# kartSPKR_rev_0.net
KiCad netlist of a schematic drawn in EAGLE
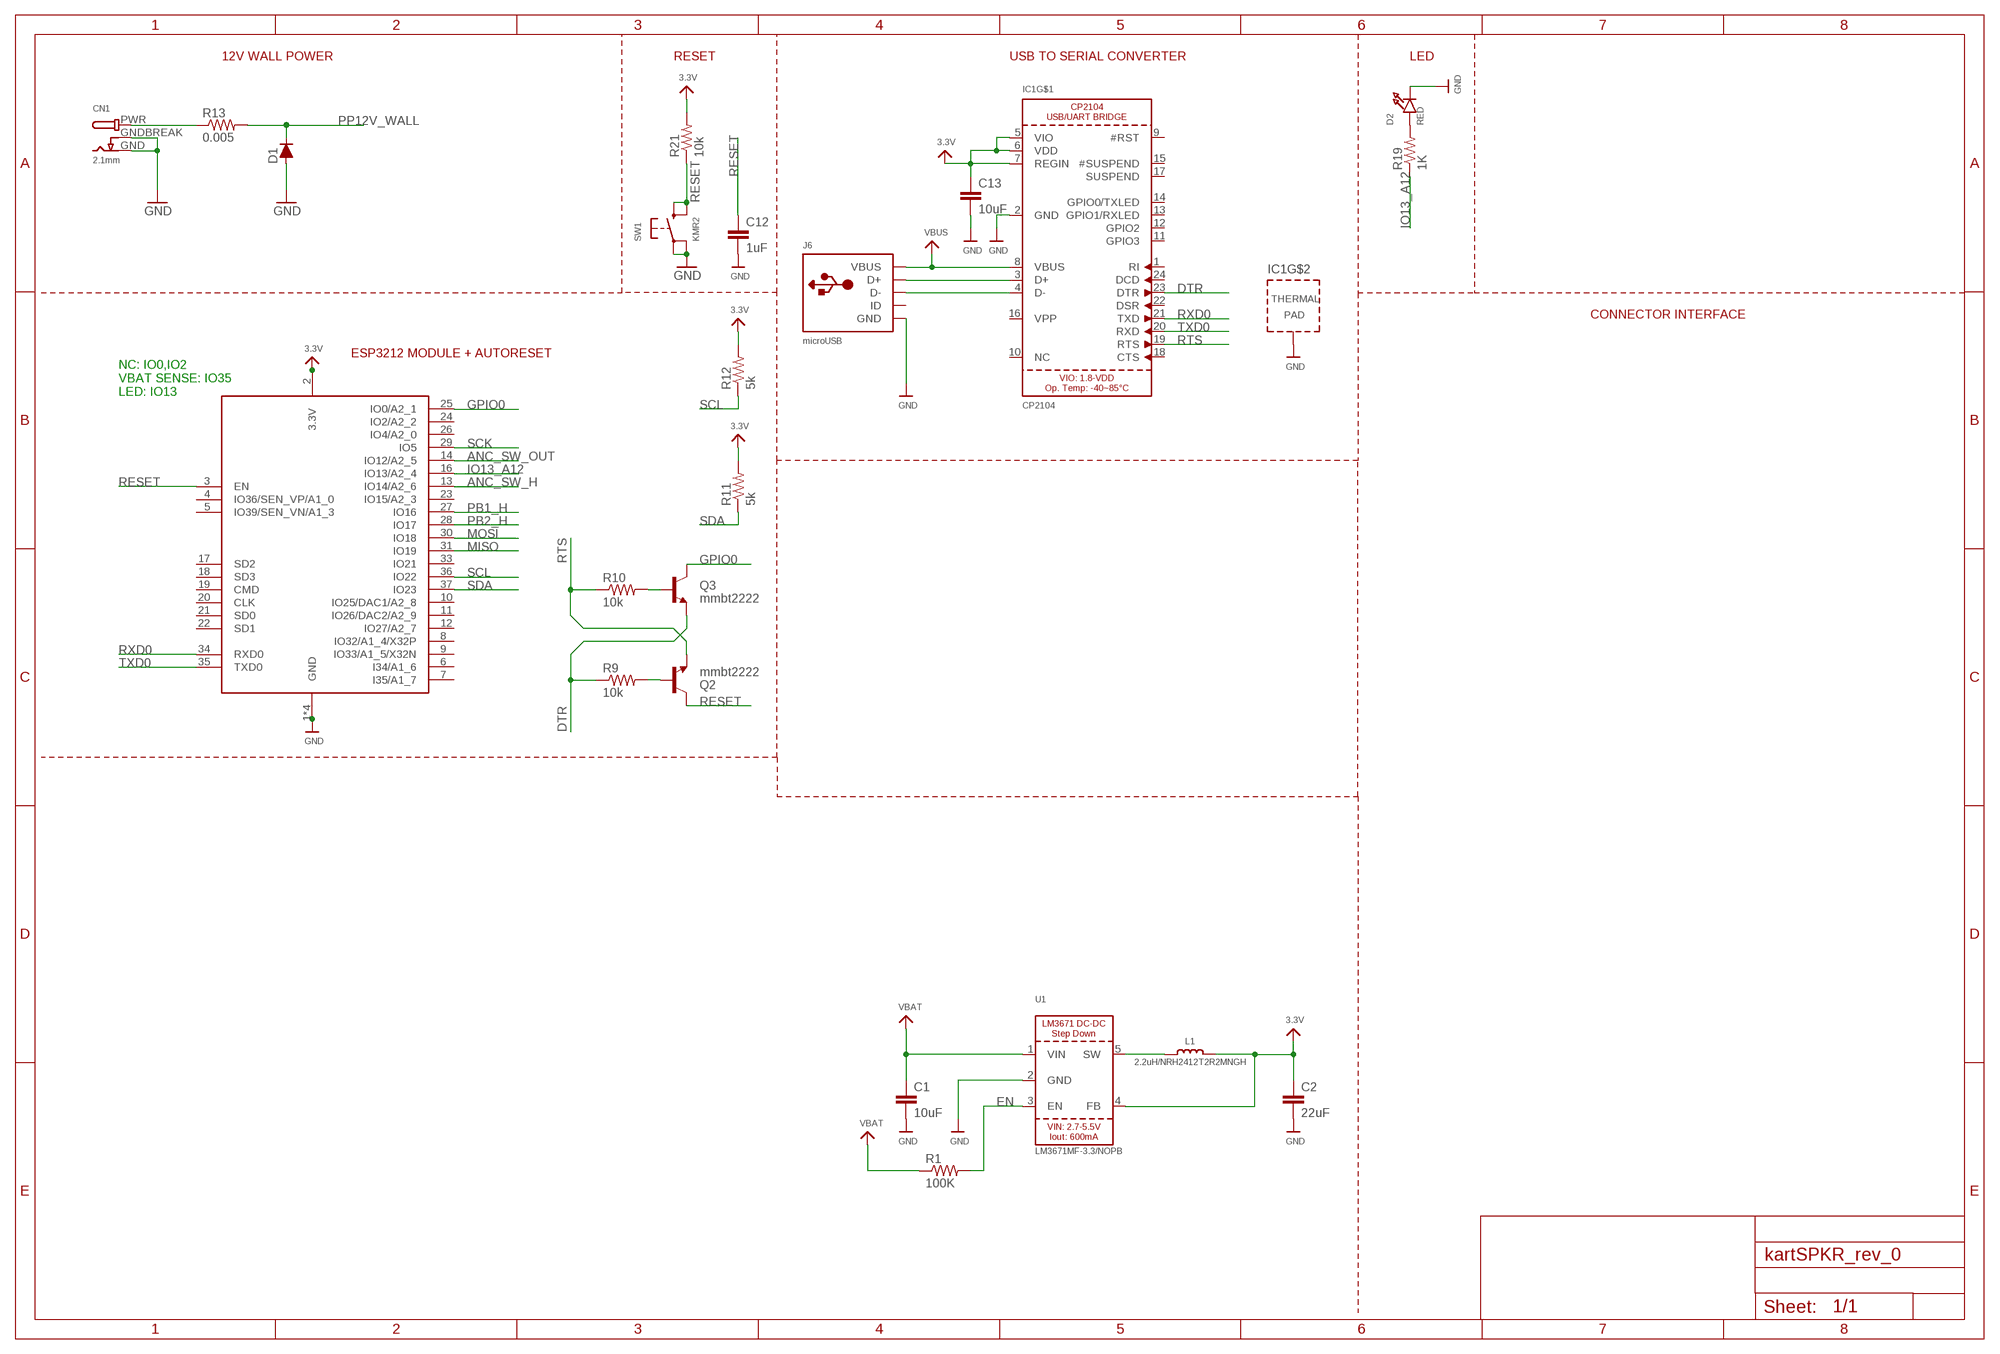
[diagram p0: schematic, sheet 1]

(export (version "E")
  (design (tool "Eeschema 10.0.6"))
  (components
    (comp (ref "C1")
      (value "10uF")
      (footprint "eagle-import:C0603")
      (libsource (lib "eagle-import") (part "C-EUC0603"))
    )
    (comp (ref "C2")
      (value "22uF")
      (footprint "eagle-import:C0603")
      (libsource (lib "eagle-import") (part "C-EUC0603"))
    )
    (comp (ref "C12")
      (value "1uF")
      (footprint "eagle-import:C0603")
      (libsource (lib "eagle-import") (part "C-EUC0603"))
    )
    (comp (ref "C13")
      (value "10uF")
      (footprint "eagle-import:C0603")
      (libsource (lib "eagle-import") (part "C-EUC0603"))
    )
    (comp (ref "CN1")
      (value "2.1mm")
      (footprint "eagle-import:DCJACK_2MM_SMT")
      (libsource (lib "eagle-import") (part "DCBARRELSMT_CORRECT"))
    )
    (comp (ref "D1")
      (value "D-FILL-SMB")
      (footprint "eagle-import:SMB")
      (libsource (lib "eagle-import") (part "D-FILL-SMB"))
    )
    (comp (ref "D2")
      (value "RED")
      (footprint "eagle-import:CHIPLED_0805_NOOUTLINE")
      (libsource (lib "eagle-import") (part "LED0805_NOOUTLINE"))
    )
    (comp (ref "IC1")
      (value "CP2104")
      (footprint "eagle-import:QFN24_4MM_SMSC")
      (libsource (lib "eagle-import") (part "CP2104"))
    )
    (comp (ref "J6")
      (value "microUSB")
      (footprint "eagle-import:4UCONN_20329")
      (libsource (lib "eagle-import") (part "USBMICRO_20329"))
    )
    (comp (ref "L1")
      (value "2.2uH/NRH2412T2R2MNGH")
      (footprint "eagle-import:INDUCTOR_TAIYOYUDEN_NRH2412T")
      (libsource (lib "eagle-import") (part "INDUCTORNRH2412T"))
    )
    (comp (ref "Q2")
      (value "mmbt2222")
      (footprint "eagle-import:SOT23-3")
      (libsource (lib "eagle-import") (part "TRANSISTOR_NPNSOT23-3"))
    )
    (comp (ref "Q3")
      (value "mmbt2222")
      (footprint "eagle-import:SOT23-3")
      (libsource (lib "eagle-import") (part "TRANSISTOR_NPNSOT23-3"))
    )
    (comp (ref "R1")
      (value "100K")
      (footprint "eagle-import:R0603")
      (libsource (lib "eagle-import") (part "R-US_R0603"))
    )
    (comp (ref "R9")
      (value "10k")
      (footprint "eagle-import:R0603")
      (libsource (lib "eagle-import") (part "R-US_R0603"))
    )
    (comp (ref "R10")
      (value "10k")
      (footprint "eagle-import:R0603")
      (libsource (lib "eagle-import") (part "R-US_R0603"))
    )
    (comp (ref "R11")
      (value "5k")
      (footprint "eagle-import:R0603")
      (libsource (lib "eagle-import") (part "R-US_R0603"))
    )
    (comp (ref "R12")
      (value "5k")
      (footprint "eagle-import:R0603")
      (libsource (lib "eagle-import") (part "R-US_R0603"))
    )
    (comp (ref "R13")
      (value "0.005")
      (footprint "eagle-import:R1206")
      (libsource (lib "eagle-import") (part "R-US_R1206"))
    )
    (comp (ref "R19")
      (value "1K")
      (footprint "eagle-import:R0603")
      (libsource (lib "eagle-import") (part "R-US_R0603"))
    )
    (comp (ref "R21")
      (value "10k")
      (footprint "eagle-import:R0603")
      (libsource (lib "eagle-import") (part "R-US_R0603"))
    )
    (comp (ref "SW1")
      (value "KMR2")
      (footprint "eagle-import:BTN_KMR2_4.6X2.8")
      (libsource (lib "eagle-import") (part "SWITCH_TACT_SMT4.6X2.8"))
    )
    (comp (ref "U1")
      (value "LM3671MF-3.3/NOPB")
      (footprint "eagle-import:SOT23-5")
      (libsource (lib "eagle-import") (part "VREG_LM3671"))
    )
    (comp (ref "X1")
      (value "ESP32_WROOM32_SKINNY")
      (footprint "eagle-import:WROOM32_SKINNY")
      (libsource (lib "eagle-import") (part "ESP32_WROOM32_SKINNY"))
    )
  )
  (nets
    (net (code "1") (name "/ANC_SW_H") (class "Default")
      (node (ref "X1") (pin "13") (pinfunction "IO14/A2_6_13") (pintype "bidirectional"))
    )
    (net (code "2") (name "/ANC_SW_OUT") (class "Default")
      (node (ref "X1") (pin "14") (pinfunction "IO12/A2_5_14") (pintype "bidirectional"))
    )
    (net (code "3") (name "/DTR") (class "Default")
      (node (ref "IC1") (pin "23") (pinfunction "DTR_23") (pintype "output"))
      (node (ref "Q3") (pin "2") (pinfunction "E_2") (pintype "passive"))
      (node (ref "R9") (pin "1") (pinfunction "1_1") (pintype "passive"))
    )
    (net (code "4") (name "/EN") (class "Default")
      (node (ref "R1") (pin "2") (pinfunction "2_2") (pintype "passive"))
      (node (ref "U1") (pin "3") (pinfunction "EN_3") (pintype "input"))
    )
    (net (code "5") (name "/GPIO0") (class "Default")
      (node (ref "Q3") (pin "3") (pinfunction "C_3") (pintype "passive"))
      (node (ref "X1") (pin "25") (pinfunction "IO0/A2_1_25") (pintype "bidirectional"))
    )
    (net (code "6") (name "/IO13_A12") (class "Default")
      (node (ref "R19") (pin "1") (pinfunction "1_1") (pintype "passive"))
      (node (ref "X1") (pin "16") (pinfunction "IO13/A2_4_16") (pintype "bidirectional"))
    )
    (net (code "7") (name "/MISO") (class "Default")
      (node (ref "X1") (pin "31") (pinfunction "IO19_31") (pintype "bidirectional"))
    )
    (net (code "8") (name "/MOSI") (class "Default")
      (node (ref "X1") (pin "30") (pinfunction "IO18_30") (pintype "bidirectional"))
    )
    (net (code "9") (name "/PB1_H") (class "Default")
      (node (ref "X1") (pin "27") (pinfunction "IO16_27") (pintype "bidirectional"))
    )
    (net (code "10") (name "/PB2_H") (class "Default")
      (node (ref "X1") (pin "28") (pinfunction "IO17_28") (pintype "bidirectional"))
    )
    (net (code "11") (name "/PP12V_WALL") (class "Default")
      (node (ref "D1") (pin "1") (pinfunction "C_1") (pintype "passive"))
      (node (ref "R13") (pin "2") (pinfunction "2_2") (pintype "passive"))
    )
    (net (code "12") (name "/RESET") (class "Default")
      (node (ref "C12") (pin "1") (pinfunction "1_1") (pintype "passive"))
      (node (ref "Q2") (pin "3") (pinfunction "C_3") (pintype "passive"))
      (node (ref "R21") (pin "1") (pinfunction "1_1") (pintype "passive"))
      (node (ref "SW1") (pin "B") (pinfunction "S_B") (pintype "passive"))
      (node (ref "SW1") (pin "B'") (pinfunction "S1_B'") (pintype "passive"))
      (node (ref "X1") (pin "3") (pinfunction "EN_3") (pintype "input"))
    )
    (net (code "13") (name "/RTS") (class "Default")
      (node (ref "IC1") (pin "19") (pinfunction "RTS_19") (pintype "output"))
      (node (ref "Q2") (pin "2") (pinfunction "E_2") (pintype "passive"))
      (node (ref "R10") (pin "1") (pinfunction "1_1") (pintype "passive"))
    )
    (net (code "14") (name "/RXD0") (class "Default")
      (node (ref "IC1") (pin "21") (pinfunction "TXD_21") (pintype "output"))
      (node (ref "X1") (pin "34") (pinfunction "RXD0_34") (pintype "input"))
    )
    (net (code "15") (name "/SCK") (class "Default")
      (node (ref "X1") (pin "29") (pinfunction "IO5_29") (pintype "bidirectional"))
    )
    (net (code "16") (name "/SCL") (class "Default")
      (node (ref "R12") (pin "1") (pinfunction "1_1") (pintype "passive"))
      (node (ref "X1") (pin "36") (pinfunction "IO22_36") (pintype "bidirectional"))
    )
    (net (code "17") (name "/SDA") (class "Default")
      (node (ref "R11") (pin "1") (pinfunction "1_1") (pintype "passive"))
      (node (ref "X1") (pin "37") (pinfunction "IO23_37") (pintype "bidirectional"))
    )
    (net (code "18") (name "/TXD0") (class "Default")
      (node (ref "IC1") (pin "20") (pinfunction "RXD_20") (pintype "input"))
      (node (ref "X1") (pin "35") (pinfunction "TXD0_35") (pintype "output"))
    )
    (net (code "19") (name "3.3V") (class "Default")
      (node (ref "C13") (pin "1") (pinfunction "1_1") (pintype "passive"))
      (node (ref "C2") (pin "1") (pinfunction "1_1") (pintype "passive"))
      (node (ref "IC1") (pin "5") (pinfunction "VIO_5") (pintype "power_in"))
      (node (ref "IC1") (pin "6") (pinfunction "VDD_6") (pintype "power_in"))
      (node (ref "IC1") (pin "7") (pinfunction "REGIN_7") (pintype "power_in"))
      (node (ref "L1") (pin "2") (pinfunction "2_2") (pintype "passive"))
      (node (ref "R11") (pin "2") (pinfunction "2_2") (pintype "passive"))
      (node (ref "R12") (pin "2") (pinfunction "2_2") (pintype "passive"))
      (node (ref "R21") (pin "2") (pinfunction "2_2") (pintype "passive"))
      (node (ref "U1") (pin "4") (pinfunction "FB_4") (pintype "power_in"))
      (node (ref "X1") (pin "2") (pinfunction "3.3V_2") (pintype "passive"))
    )
    (net (code "20") (name "GND") (class "Default")
      (node (ref "C1") (pin "2") (pinfunction "2_2") (pintype "passive"))
      (node (ref "C12") (pin "2") (pinfunction "2_2") (pintype "passive"))
      (node (ref "C13") (pin "2") (pinfunction "2_2") (pintype "passive"))
      (node (ref "C2") (pin "2") (pinfunction "2_2") (pintype "passive"))
      (node (ref "CN1") (pin "GND") (pinfunction "GND_GND") (pintype "power_in"))
      (node (ref "CN1") (pin "GNDBREAK") (pinfunction "GNDBREAK_GNDBREAK") (pintype "power_in"))
      (node (ref "D1") (pin "2") (pinfunction "A_2") (pintype "passive"))
      (node (ref "D2") (pin "C") (pinfunction "C_C") (pintype "passive"))
      (node (ref "IC1") (pin "2") (pinfunction "GND_2") (pintype "power_in"))
      (node (ref "IC1") (pin "THERM") (pinfunction "TP_THERM") (pintype "power_in"))
      (node (ref "J6") (pin "BASE@1") (pinfunction "GND_BASE@1") (pintype "power_in"))
      (node (ref "J6") (pin "BASE@2") (pinfunction "GND_BASE@2") (pintype "power_in"))
      (node (ref "J6") (pin "GND") (pinfunction "GND_GND") (pintype "power_in"))
      (node (ref "J6") (pin "SPRT@1") (pinfunction "GND_SPRT@1") (pintype "power_in"))
      (node (ref "J6") (pin "SPRT@2") (pinfunction "GND_SPRT@2") (pintype "power_in"))
      (node (ref "J6") (pin "SPRT@3") (pinfunction "GND_SPRT@3") (pintype "power_in"))
      (node (ref "J6") (pin "SPRT@4") (pinfunction "GND_SPRT@4") (pintype "power_in"))
      (node (ref "SW1") (pin "A") (pinfunction "P_A") (pintype "passive"))
      (node (ref "SW1") (pin "A'") (pinfunction "P1_A'") (pintype "passive"))
      (node (ref "U1") (pin "2") (pinfunction "GND_2") (pintype "power_in"))
      (node (ref "X1") (pin "1") (pinfunction "GND_1") (pintype "passive"))
      (node (ref "X1") (pin "15") (pinfunction "GND_15") (pintype "passive"))
      (node (ref "X1") (pin "38") (pinfunction "GND_38") (pintype "passive"))
      (node (ref "X1") (pin "P$1") (pinfunction "GND_P$1") (pintype "passive"))
    )
    (net (code "21") (name "Net-(CN1-PadPWR)") (class "Default")
      (node (ref "CN1") (pin "PWR") (pinfunction "PWR_PWR") (pintype "power_in"))
      (node (ref "R13") (pin "1") (pinfunction "1_1") (pintype "passive"))
    )
    (net (code "22") (name "Net-(D2-PadA)") (class "Default")
      (node (ref "D2") (pin "A") (pinfunction "A_A") (pintype "passive"))
      (node (ref "R19") (pin "2") (pinfunction "2_2") (pintype "passive"))
    )
    (net (code "23") (name "Net-(IC1A-D+)") (class "Default")
      (node (ref "IC1") (pin "3") (pinfunction "D+_3") (pintype "bidirectional"))
      (node (ref "J6") (pin "D+") (pinfunction "D+_D+") (pintype "bidirectional"))
    )
    (net (code "24") (name "Net-(IC1A-D-)") (class "Default")
      (node (ref "IC1") (pin "4") (pinfunction "D-_4") (pintype "bidirectional"))
      (node (ref "J6") (pin "D-") (pinfunction "D-_D-") (pintype "bidirectional"))
    )
    (net (code "25") (name "Net-(Q2-B)") (class "Default")
      (node (ref "Q2") (pin "1") (pinfunction "B_1") (pintype "passive"))
      (node (ref "R9") (pin "2") (pinfunction "2_2") (pintype "passive"))
    )
    (net (code "26") (name "Net-(Q3-B)") (class "Default")
      (node (ref "Q3") (pin "1") (pinfunction "B_1") (pintype "passive"))
      (node (ref "R10") (pin "2") (pinfunction "2_2") (pintype "passive"))
    )
    (net (code "27") (name "Net-(U1-SW)") (class "Default")
      (node (ref "L1") (pin "1") (pinfunction "1_1") (pintype "passive"))
      (node (ref "U1") (pin "5") (pinfunction "SW_5") (pintype "output"))
    )
    (net (code "28") (name "VBAT") (class "Default")
      (node (ref "C1") (pin "1") (pinfunction "1_1") (pintype "passive"))
      (node (ref "R1") (pin "1") (pinfunction "1_1") (pintype "passive"))
      (node (ref "U1") (pin "1") (pinfunction "VIN_1") (pintype "power_in"))
    )
    (net (code "29") (name "VBUS") (class "Default")
      (node (ref "IC1") (pin "8") (pinfunction "VBUS_8") (pintype "power_in"))
      (node (ref "J6") (pin "VBUS") (pinfunction "VBUS_VBUS") (pintype "power_in"))
    )
    (net (code "30") (name "unconnected-(IC1A-#RST-Pad9)") (class "Default")
      (node (ref "IC1") (pin "9") (pinfunction "#RST_9") (pintype "bidirectional"))
    )
    (net (code "31") (name "unconnected-(IC1A-#SUSPEND-Pad15)") (class "Default")
      (node (ref "IC1") (pin "15") (pinfunction "#SUSPEND_15") (pintype "output"))
    )
    (net (code "32") (name "unconnected-(IC1A-CTS-Pad18)") (class "Default")
      (node (ref "IC1") (pin "18") (pinfunction "CTS_18") (pintype "input"))
    )
    (net (code "33") (name "unconnected-(IC1A-DCD-Pad24)") (class "Default")
      (node (ref "IC1") (pin "24") (pinfunction "DCD_24") (pintype "input"))
    )
    (net (code "34") (name "unconnected-(IC1A-DSR-Pad22)") (class "Default")
      (node (ref "IC1") (pin "22") (pinfunction "DSR_22") (pintype "input"))
    )
    (net (code "35") (name "unconnected-(IC1A-GPIO0{slash}TXLED-Pad14)") (class "Default")
      (node (ref "IC1") (pin "14") (pinfunction "GPIO0/TXLED_14") (pintype "bidirectional"))
    )
    (net (code "36") (name "unconnected-(IC1A-GPIO1{slash}RXLED-Pad13)") (class "Default")
      (node (ref "IC1") (pin "13") (pinfunction "GPIO1/RXLED_13") (pintype "bidirectional"))
    )
    (net (code "37") (name "unconnected-(IC1A-GPIO2-Pad12)") (class "Default")
      (node (ref "IC1") (pin "12") (pinfunction "GPIO2_12") (pintype "bidirectional"))
    )
    (net (code "38") (name "unconnected-(IC1A-GPIO3-Pad11)") (class "Default")
      (node (ref "IC1") (pin "11") (pinfunction "GPIO3_11") (pintype "bidirectional"))
    )
    (net (code "39") (name "unconnected-(IC1A-NC-Pad10)") (class "Default")
      (node (ref "IC1") (pin "10") (pinfunction "NC_10") (pintype "no_connect"))
    )
    (net (code "40") (name "unconnected-(IC1A-RI-Pad1)") (class "Default")
      (node (ref "IC1") (pin "1") (pinfunction "RI_1") (pintype "input"))
    )
    (net (code "41") (name "unconnected-(IC1A-SUSPEND-Pad17)") (class "Default")
      (node (ref "IC1") (pin "17") (pinfunction "SUSPEND_17") (pintype "output"))
    )
    (net (code "42") (name "unconnected-(IC1A-VPP-Pad16)") (class "Default")
      (node (ref "IC1") (pin "16") (pinfunction "VPP_16") (pintype "bidirectional"))
    )
    (net (code "43") (name "unconnected-(J6-PadID)") (class "Default")
      (node (ref "J6") (pin "ID") (pinfunction "ID_ID") (pintype "bidirectional"))
    )
    (net (code "44") (name "unconnected-(X1-CLK-Pad20)") (class "Default")
      (node (ref "X1") (pin "20") (pinfunction "CLK_20") (pintype "bidirectional"))
    )
    (net (code "45") (name "unconnected-(X1-CMD-Pad19)") (class "Default")
      (node (ref "X1") (pin "19") (pinfunction "CMD_19") (pintype "bidirectional"))
    )
    (net (code "46") (name "unconnected-(X1-I34{slash}A1_6-Pad6)") (class "Default")
      (node (ref "X1") (pin "6") (pinfunction "I34/A1_6_6") (pintype "bidirectional"))
    )
    (net (code "47") (name "unconnected-(X1-I35{slash}A1_7-Pad7)") (class "Default")
      (node (ref "X1") (pin "7") (pinfunction "I35/A1_7_7") (pintype "bidirectional"))
    )
    (net (code "48") (name "unconnected-(X1-IO2{slash}A2_2-Pad24)") (class "Default")
      (node (ref "X1") (pin "24") (pinfunction "IO2/A2_2_24") (pintype "bidirectional"))
    )
    (net (code "49") (name "unconnected-(X1-IO4{slash}A2_0-Pad26)") (class "Default")
      (node (ref "X1") (pin "26") (pinfunction "IO4/A2_0_26") (pintype "bidirectional"))
    )
    (net (code "50") (name "unconnected-(X1-IO15{slash}A2_3-Pad23)") (class "Default")
      (node (ref "X1") (pin "23") (pinfunction "IO15/A2_3_23") (pintype "bidirectional"))
    )
    (net (code "51") (name "unconnected-(X1-IO21-Pad33)") (class "Default")
      (node (ref "X1") (pin "33") (pinfunction "IO21_33") (pintype "bidirectional"))
    )
    (net (code "52") (name "unconnected-(X1-IO25{slash}DAC1{slash}A2_8-Pad10)") (class "Default")
      (node (ref "X1") (pin "10") (pinfunction "IO25/DAC1/A2_8_10") (pintype "bidirectional"))
    )
    (net (code "53") (name "unconnected-(X1-IO26{slash}DAC2{slash}A2_9-Pad11)") (class "Default")
      (node (ref "X1") (pin "11") (pinfunction "IO26/DAC2/A2_9_11") (pintype "bidirectional"))
    )
    (net (code "54") (name "unconnected-(X1-IO27{slash}A2_7-Pad12)") (class "Default")
      (node (ref "X1") (pin "12") (pinfunction "IO27/A2_7_12") (pintype "bidirectional"))
    )
    (net (code "55") (name "unconnected-(X1-IO32{slash}A1_4{slash}X32P-Pad8)") (class "Default")
      (node (ref "X1") (pin "8") (pinfunction "IO32/A1_4/X32P_8") (pintype "bidirectional"))
    )
    (net (code "56") (name "unconnected-(X1-IO33{slash}A1_5{slash}X32N-Pad9)") (class "Default")
      (node (ref "X1") (pin "9") (pinfunction "IO33/A1_5/X32N_9") (pintype "bidirectional"))
    )
    (net (code "57") (name "unconnected-(X1-IO36{slash}SEN_VP{slash}A1_0-Pad4)") (class "Default")
      (node (ref "X1") (pin "4") (pinfunction "IO36/SEN_VP/A1_0_4") (pintype "passive"))
    )
    (net (code "58") (name "unconnected-(X1-IO39{slash}SEN_VN{slash}A1_3-Pad5)") (class "Default")
      (node (ref "X1") (pin "5") (pinfunction "IO39/SEN_VN/A1_3_5") (pintype "passive"))
    )
    (net (code "59") (name "unconnected-(X1-SD0-Pad21)") (class "Default")
      (node (ref "X1") (pin "21") (pinfunction "SD0_21") (pintype "bidirectional"))
    )
    (net (code "60") (name "unconnected-(X1-SD1-Pad22)") (class "Default")
      (node (ref "X1") (pin "22") (pinfunction "SD1_22") (pintype "bidirectional"))
    )
    (net (code "61") (name "unconnected-(X1-SD2-Pad17)") (class "Default")
      (node (ref "X1") (pin "17") (pinfunction "SD2_17") (pintype "bidirectional"))
    )
    (net (code "62") (name "unconnected-(X1-SD3-Pad18)") (class "Default")
      (node (ref "X1") (pin "18") (pinfunction "SD3_18") (pintype "bidirectional"))
    )
  )
)
